# batboard_rev2.net
KiCad netlist of a schematic drawn in EAGLE
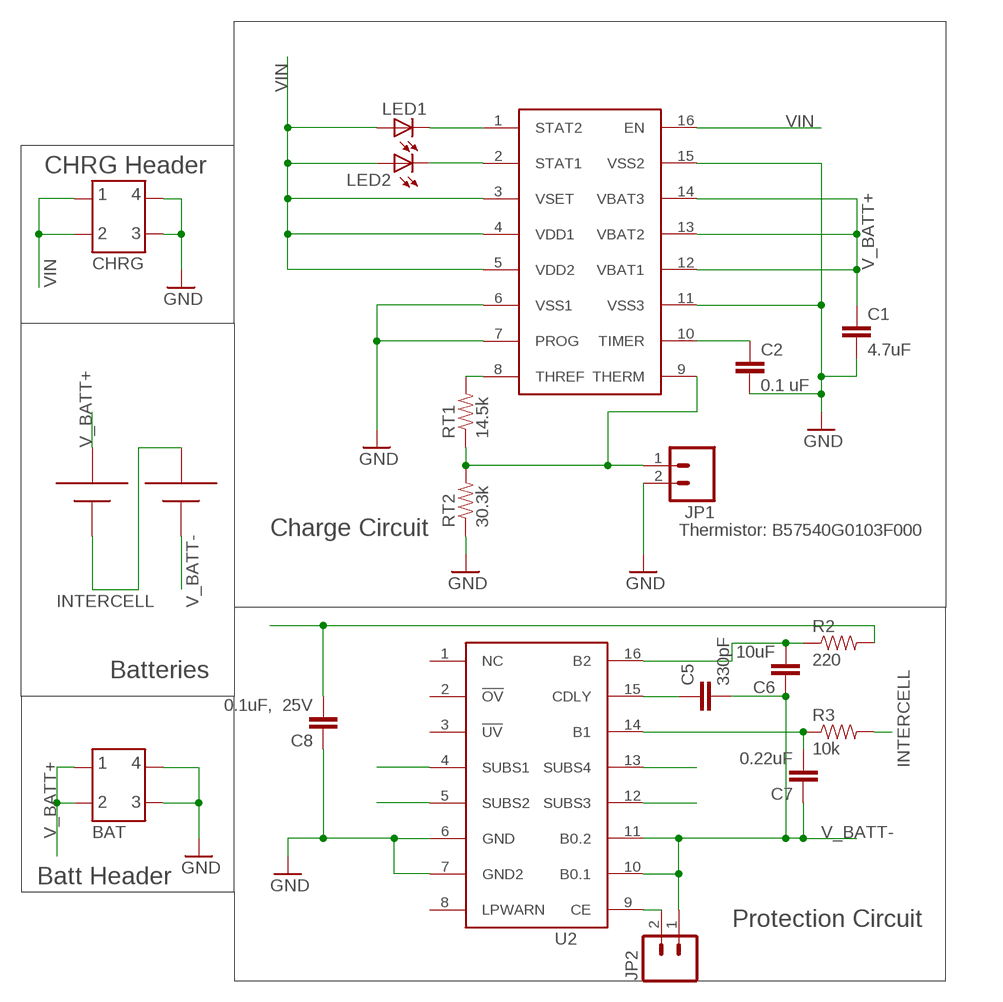
[diagram p0: schematic, sheet 1]

(export (version "E")
  (design (tool "Eeschema 10.0.6"))
  (components
    (comp (ref "BAT")
      (value "C-GRID-71308")
      (footprint "eagle-import:4HEAD_MOLEX_C71308")
      (libsource (lib "eagle-import") (part "C-GRID-71308"))
    )
    (comp (ref "C1")
      (value "4.7uF")
      (footprint "eagle-import:0805")
      (libsource (lib "eagle-import") (part "CAP0805"))
    )
    (comp (ref "C2")
      (value "0.1 uF")
      (footprint "eagle-import:0805")
      (libsource (lib "eagle-import") (part "CAP0805"))
    )
    (comp (ref "C5")
      (value "330pF")
      (footprint "eagle-import:0805")
      (libsource (lib "eagle-import") (part "CAP0805"))
    )
    (comp (ref "C6")
      (value "10uF")
      (footprint "eagle-import:0805")
      (libsource (lib "eagle-import") (part "CAP0805"))
    )
    (comp (ref "C7")
      (value "0.22uF")
      (footprint "eagle-import:0805")
      (libsource (lib "eagle-import") (part "CAP0805"))
    )
    (comp (ref "C8")
      (value "0.1uF, 25V")
      (footprint "eagle-import:0805")
      (libsource (lib "eagle-import") (part "CAP0805"))
    )
    (comp (ref "CHRG")
      (value "C-GRID-71308")
      (footprint "eagle-import:4HEAD_MOLEX_C71308")
      (libsource (lib "eagle-import") (part "C-GRID-71308"))
    )
    (comp (ref "JP1")
      (value "M02PTH")
      (footprint "eagle-import:1X02")
      (libsource (lib "eagle-import") (part "M02PTH"))
    )
    (comp (ref "JP2")
      (value "M02PTH")
      (footprint "eagle-import:1X02")
      (libsource (lib "eagle-import") (part "M02PTH"))
    )
    (comp (ref "LED1")
      (value "LED1206")
      (footprint "eagle-import:LED-1206")
      (libsource (lib "eagle-import") (part "LED1206"))
    )
    (comp (ref "LED2")
      (value "LED1206")
      (footprint "eagle-import:LED-1206")
      (libsource (lib "eagle-import") (part "LED1206"))
    )
    (comp (ref "R2")
      (value "220")
      (footprint "eagle-import:0603-RES")
      (libsource (lib "eagle-import") (part "RESISTOR0603-RES"))
    )
    (comp (ref "R3")
      (value "10k")
      (footprint "eagle-import:0603-RES")
      (libsource (lib "eagle-import") (part "RESISTOR0603-RES"))
    )
    (comp (ref "RT1")
      (value "14.5k")
      (footprint "eagle-import:0603-RES")
      (libsource (lib "eagle-import") (part "RESISTOR0603-RES"))
    )
    (comp (ref "RT2")
      (value "30.3k")
      (footprint "eagle-import:0603-RES")
      (libsource (lib "eagle-import") (part "RESISTOR0603-RES"))
    )
    (comp (ref "U$1")
      (value "BK-18650-PC4")
      (footprint "eagle-import:18650-PC4")
      (libsource (lib "eagle-import") (part "BK-18650-PC4"))
    )
    (comp (ref "U1")
      (value "MCP73862")
      (footprint "eagle-import:SOIC-16")
      (libsource (lib "eagle-import") (part "MCP73862"))
    )
    (comp (ref "U2")
      (value "UCC3911")
      (footprint "eagle-import:SOIC-16")
      (libsource (lib "eagle-import") (part "UCC3911"))
    )
  )
  (nets
    (net (code "1") (name "/HSINK") (class "Default")
      (node (ref "U2") (pin "12") (pinfunction "SUBS3_12") (pintype "bidirectional"))
      (node (ref "U2") (pin "13") (pinfunction "SUBS4_13") (pintype "bidirectional"))
      (node (ref "U2") (pin "4") (pinfunction "SUBS1_4") (pintype "bidirectional"))
      (node (ref "U2") (pin "5") (pinfunction "SUBS2_5") (pintype "bidirectional"))
    )
    (net (code "2") (name "/INTERCELL") (class "Default")
      (node (ref "R3") (pin "2") (pinfunction "2_2") (pintype "passive"))
      (node (ref "U$1") (pin "+2") (pinfunction "+2_+2") (pintype "bidirectional"))
      (node (ref "U$1") (pin "-1") (pinfunction "-1_-1") (pintype "bidirectional"))
    )
    (net (code "3") (name "/VIN") (class "Default")
      (node (ref "CHRG") (pin "1") (pinfunction "1_1") (pintype "bidirectional"))
      (node (ref "CHRG") (pin "2") (pinfunction "2_2") (pintype "bidirectional"))
      (node (ref "LED1") (pin "A") (pinfunction "A_A") (pintype "passive"))
      (node (ref "LED2") (pin "A") (pinfunction "A_A") (pintype "passive"))
      (node (ref "U1") (pin "16") (pinfunction "EN_16") (pintype "bidirectional"))
      (node (ref "U1") (pin "3") (pinfunction "VSET_3") (pintype "bidirectional"))
      (node (ref "U1") (pin "4") (pinfunction "VDD1_4") (pintype "bidirectional"))
      (node (ref "U1") (pin "5") (pinfunction "VDD2_5") (pintype "bidirectional"))
    )
    (net (code "4") (name "/V_BATT+") (class "Default")
      (node (ref "BAT") (pin "1") (pinfunction "1_1") (pintype "bidirectional"))
      (node (ref "BAT") (pin "2") (pinfunction "2_2") (pintype "bidirectional"))
      (node (ref "C1") (pin "1") (pinfunction "1_1") (pintype "passive"))
      (node (ref "C8") (pin "2") (pinfunction "2_2") (pintype "passive"))
      (node (ref "R2") (pin "2") (pinfunction "2_2") (pintype "passive"))
      (node (ref "U$1") (pin "+1") (pinfunction "+1_+1") (pintype "bidirectional"))
      (node (ref "U1") (pin "12") (pinfunction "VBAT1_12") (pintype "bidirectional"))
      (node (ref "U1") (pin "13") (pinfunction "VBAT2_13") (pintype "bidirectional"))
      (node (ref "U1") (pin "14") (pinfunction "VBAT3_14") (pintype "bidirectional"))
    )
    (net (code "5") (name "/V_BATT-") (class "Default")
      (node (ref "C5") (pin "2") (pinfunction "2_2") (pintype "passive"))
      (node (ref "C6") (pin "1") (pinfunction "1_1") (pintype "passive"))
      (node (ref "C7") (pin "1") (pinfunction "1_1") (pintype "passive"))
      (node (ref "JP2") (pin "1") (pinfunction "1_1") (pintype "passive"))
      (node (ref "U$1") (pin "-2") (pinfunction "-2_-2") (pintype "bidirectional"))
      (node (ref "U2") (pin "10") (pinfunction "B0.1_10") (pintype "bidirectional"))
      (node (ref "U2") (pin "11") (pinfunction "B0.2_11") (pintype "bidirectional"))
    )
    (net (code "6") (name "GND") (class "Default")
      (node (ref "BAT") (pin "3") (pinfunction "3_3") (pintype "bidirectional"))
      (node (ref "BAT") (pin "4") (pinfunction "4_4") (pintype "bidirectional"))
      (node (ref "C1") (pin "2") (pinfunction "2_2") (pintype "passive"))
      (node (ref "C2") (pin "2") (pinfunction "2_2") (pintype "passive"))
      (node (ref "C8") (pin "1") (pinfunction "1_1") (pintype "passive"))
      (node (ref "CHRG") (pin "3") (pinfunction "3_3") (pintype "bidirectional"))
      (node (ref "CHRG") (pin "4") (pinfunction "4_4") (pintype "bidirectional"))
      (node (ref "JP1") (pin "2") (pinfunction "2_2") (pintype "passive"))
      (node (ref "RT2") (pin "1") (pinfunction "1_1") (pintype "passive"))
      (node (ref "U1") (pin "11") (pinfunction "VSS3_11") (pintype "bidirectional"))
      (node (ref "U1") (pin "15") (pinfunction "VSS2_15") (pintype "bidirectional"))
      (node (ref "U1") (pin "6") (pinfunction "VSS1_6") (pintype "bidirectional"))
      (node (ref "U1") (pin "7") (pinfunction "PROG_7") (pintype "bidirectional"))
      (node (ref "U2") (pin "6") (pinfunction "GND_6") (pintype "bidirectional"))
      (node (ref "U2") (pin "7") (pinfunction "GND2_7") (pintype "bidirectional"))
    )
    (net (code "7") (name "Net-(U1-STAT1)") (class "Default")
      (node (ref "LED2") (pin "C") (pinfunction "C_C") (pintype "passive"))
      (node (ref "U1") (pin "2") (pinfunction "STAT1_2") (pintype "bidirectional"))
    )
    (net (code "8") (name "Net-(U1-STAT2)") (class "Default")
      (node (ref "LED1") (pin "C") (pinfunction "C_C") (pintype "passive"))
      (node (ref "U1") (pin "1") (pinfunction "STAT2_1") (pintype "bidirectional"))
    )
    (net (code "9") (name "Net-(U1-THERM)") (class "Default")
      (node (ref "JP1") (pin "1") (pinfunction "1_1") (pintype "passive"))
      (node (ref "RT1") (pin "1") (pinfunction "1_1") (pintype "passive"))
      (node (ref "RT2") (pin "2") (pinfunction "2_2") (pintype "passive"))
      (node (ref "U1") (pin "9") (pinfunction "THERM_9") (pintype "bidirectional"))
    )
    (net (code "10") (name "Net-(U1-THREF)") (class "Default")
      (node (ref "RT1") (pin "2") (pinfunction "2_2") (pintype "passive"))
      (node (ref "U1") (pin "8") (pinfunction "THREF_8") (pintype "bidirectional"))
    )
    (net (code "11") (name "Net-(U1-TIMER)") (class "Default")
      (node (ref "C2") (pin "1") (pinfunction "1_1") (pintype "passive"))
      (node (ref "U1") (pin "10") (pinfunction "TIMER_10") (pintype "bidirectional"))
    )
    (net (code "12") (name "Net-(U2-B1)") (class "Default")
      (node (ref "C7") (pin "2") (pinfunction "2_2") (pintype "passive"))
      (node (ref "R3") (pin "1") (pinfunction "1_1") (pintype "passive"))
      (node (ref "U2") (pin "14") (pinfunction "B1_14") (pintype "bidirectional"))
    )
    (net (code "13") (name "Net-(U2-B2)") (class "Default")
      (node (ref "C6") (pin "2") (pinfunction "2_2") (pintype "passive"))
      (node (ref "R2") (pin "1") (pinfunction "1_1") (pintype "passive"))
      (node (ref "U2") (pin "16") (pinfunction "B2_16") (pintype "bidirectional"))
    )
    (net (code "14") (name "Net-(U2-CDLY)") (class "Default")
      (node (ref "C5") (pin "1") (pinfunction "1_1") (pintype "passive"))
      (node (ref "U2") (pin "15") (pinfunction "CDLY_15") (pintype "bidirectional"))
    )
    (net (code "15") (name "Net-(U2-CE)") (class "Default")
      (node (ref "JP2") (pin "2") (pinfunction "2_2") (pintype "passive"))
      (node (ref "U2") (pin "9") (pinfunction "CE_9") (pintype "bidirectional"))
    )
    (net (code "16") (name "unconnected-(U2-LPWARN-Pad8)") (class "Default")
      (node (ref "U2") (pin "8") (pinfunction "LPWARN_8") (pintype "bidirectional"))
    )
    (net (code "17") (name "unconnected-(U2-NC-Pad1)") (class "Default")
      (node (ref "U2") (pin "1") (pinfunction "NC_1") (pintype "bidirectional"))
    )
    (net (code "18") (name "unconnected-(U2-~{OV}-Pad2)") (class "Default")
      (node (ref "U2") (pin "2") (pinfunction "~{OV}_2") (pintype "bidirectional"))
    )
    (net (code "19") (name "unconnected-(U2-~{UV}-Pad3)") (class "Default")
      (node (ref "U2") (pin "3") (pinfunction "~{UV}_3") (pintype "bidirectional"))
    )
  )
)
